# Main.net
KiCad netlist of a schematic drawn in EAGLE
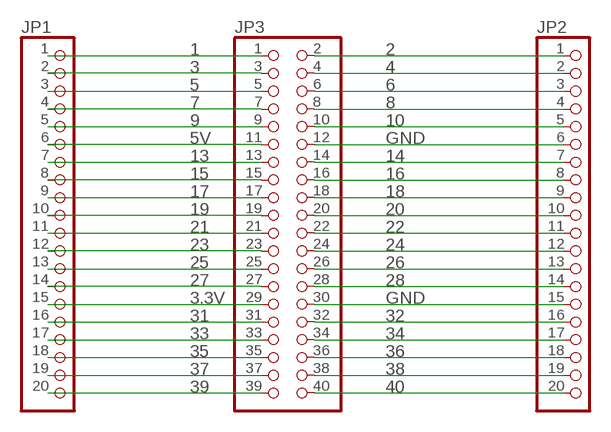
[diagram p0: schematic, sheet 1]

(export (version "E")
  (design (tool "Eeschema 10.0.6"))
  (components
    (comp (ref "JP1")
      (value "PINHD-1X20")
      (footprint "eagle-import:1X20")
      (libsource (lib "eagle-import") (part "PINHD-1X20"))
    )
    (comp (ref "JP2")
      (value "PINHD-1X20")
      (footprint "eagle-import:1X20")
      (libsource (lib "eagle-import") (part "PINHD-1X20"))
    )
    (comp (ref "JP3")
      (value "PINHD-2X20")
      (footprint "eagle-import:2X20")
      (libsource (lib "eagle-import") (part "PINHD-2X20"))
    )
  )
  (nets
    (net (code "1") (name "/1") (class "Default")
      (node (ref "JP1") (pin "1") (pinfunction "1_1") (pintype "passive"))
      (node (ref "JP3") (pin "1") (pinfunction "1_1") (pintype "passive"))
    )
    (net (code "2") (name "/2") (class "Default")
      (node (ref "JP2") (pin "1") (pinfunction "1_1") (pintype "passive"))
      (node (ref "JP3") (pin "2") (pinfunction "2_2") (pintype "passive"))
    )
    (net (code "3") (name "/3") (class "Default")
      (node (ref "JP1") (pin "2") (pinfunction "2_2") (pintype "passive"))
      (node (ref "JP3") (pin "3") (pinfunction "3_3") (pintype "passive"))
    )
    (net (code "4") (name "/3.3V") (class "Default")
      (node (ref "JP1") (pin "15") (pinfunction "15_15") (pintype "passive"))
      (node (ref "JP3") (pin "29") (pinfunction "29_29") (pintype "passive"))
    )
    (net (code "5") (name "/4") (class "Default")
      (node (ref "JP2") (pin "2") (pinfunction "2_2") (pintype "passive"))
      (node (ref "JP3") (pin "4") (pinfunction "4_4") (pintype "passive"))
    )
    (net (code "6") (name "/5") (class "Default")
      (node (ref "JP1") (pin "3") (pinfunction "3_3") (pintype "passive"))
      (node (ref "JP3") (pin "5") (pinfunction "5_5") (pintype "passive"))
    )
    (net (code "7") (name "/5V") (class "Default")
      (node (ref "JP1") (pin "6") (pinfunction "6_6") (pintype "passive"))
      (node (ref "JP3") (pin "11") (pinfunction "11_11") (pintype "passive"))
    )
    (net (code "8") (name "/6") (class "Default")
      (node (ref "JP2") (pin "3") (pinfunction "3_3") (pintype "passive"))
      (node (ref "JP3") (pin "6") (pinfunction "6_6") (pintype "passive"))
    )
    (net (code "9") (name "/7") (class "Default")
      (node (ref "JP1") (pin "4") (pinfunction "4_4") (pintype "passive"))
      (node (ref "JP3") (pin "7") (pinfunction "7_7") (pintype "passive"))
    )
    (net (code "10") (name "/8") (class "Default")
      (node (ref "JP2") (pin "4") (pinfunction "4_4") (pintype "passive"))
      (node (ref "JP3") (pin "8") (pinfunction "8_8") (pintype "passive"))
    )
    (net (code "11") (name "/9") (class "Default")
      (node (ref "JP1") (pin "5") (pinfunction "5_5") (pintype "passive"))
      (node (ref "JP3") (pin "9") (pinfunction "9_9") (pintype "passive"))
    )
    (net (code "12") (name "/10") (class "Default")
      (node (ref "JP2") (pin "5") (pinfunction "5_5") (pintype "passive"))
      (node (ref "JP3") (pin "10") (pinfunction "10_10") (pintype "passive"))
    )
    (net (code "13") (name "/13") (class "Default")
      (node (ref "JP1") (pin "7") (pinfunction "7_7") (pintype "passive"))
      (node (ref "JP3") (pin "13") (pinfunction "13_13") (pintype "passive"))
    )
    (net (code "14") (name "/14") (class "Default")
      (node (ref "JP2") (pin "7") (pinfunction "7_7") (pintype "passive"))
      (node (ref "JP3") (pin "14") (pinfunction "14_14") (pintype "passive"))
    )
    (net (code "15") (name "/15") (class "Default")
      (node (ref "JP1") (pin "8") (pinfunction "8_8") (pintype "passive"))
      (node (ref "JP3") (pin "15") (pinfunction "15_15") (pintype "passive"))
    )
    (net (code "16") (name "/16") (class "Default")
      (node (ref "JP2") (pin "8") (pinfunction "8_8") (pintype "passive"))
      (node (ref "JP3") (pin "16") (pinfunction "16_16") (pintype "passive"))
    )
    (net (code "17") (name "/17") (class "Default")
      (node (ref "JP1") (pin "9") (pinfunction "9_9") (pintype "passive"))
      (node (ref "JP3") (pin "17") (pinfunction "17_17") (pintype "passive"))
    )
    (net (code "18") (name "/18") (class "Default")
      (node (ref "JP2") (pin "9") (pinfunction "9_9") (pintype "passive"))
      (node (ref "JP3") (pin "18") (pinfunction "18_18") (pintype "passive"))
    )
    (net (code "19") (name "/19") (class "Default")
      (node (ref "JP1") (pin "10") (pinfunction "10_10") (pintype "passive"))
      (node (ref "JP3") (pin "19") (pinfunction "19_19") (pintype "passive"))
    )
    (net (code "20") (name "/20") (class "Default")
      (node (ref "JP2") (pin "10") (pinfunction "10_10") (pintype "passive"))
      (node (ref "JP3") (pin "20") (pinfunction "20_20") (pintype "passive"))
    )
    (net (code "21") (name "/21") (class "Default")
      (node (ref "JP1") (pin "11") (pinfunction "11_11") (pintype "passive"))
      (node (ref "JP3") (pin "21") (pinfunction "21_21") (pintype "passive"))
    )
    (net (code "22") (name "/22") (class "Default")
      (node (ref "JP2") (pin "11") (pinfunction "11_11") (pintype "passive"))
      (node (ref "JP3") (pin "22") (pinfunction "22_22") (pintype "passive"))
    )
    (net (code "23") (name "/23") (class "Default")
      (node (ref "JP1") (pin "12") (pinfunction "12_12") (pintype "passive"))
      (node (ref "JP3") (pin "23") (pinfunction "23_23") (pintype "passive"))
    )
    (net (code "24") (name "/24") (class "Default")
      (node (ref "JP2") (pin "12") (pinfunction "12_12") (pintype "passive"))
      (node (ref "JP3") (pin "24") (pinfunction "24_24") (pintype "passive"))
    )
    (net (code "25") (name "/25") (class "Default")
      (node (ref "JP1") (pin "13") (pinfunction "13_13") (pintype "passive"))
      (node (ref "JP3") (pin "25") (pinfunction "25_25") (pintype "passive"))
    )
    (net (code "26") (name "/26") (class "Default")
      (node (ref "JP2") (pin "13") (pinfunction "13_13") (pintype "passive"))
      (node (ref "JP3") (pin "26") (pinfunction "26_26") (pintype "passive"))
    )
    (net (code "27") (name "/27") (class "Default")
      (node (ref "JP1") (pin "14") (pinfunction "14_14") (pintype "passive"))
      (node (ref "JP3") (pin "27") (pinfunction "27_27") (pintype "passive"))
    )
    (net (code "28") (name "/28") (class "Default")
      (node (ref "JP2") (pin "14") (pinfunction "14_14") (pintype "passive"))
      (node (ref "JP3") (pin "28") (pinfunction "28_28") (pintype "passive"))
    )
    (net (code "29") (name "/31") (class "Default")
      (node (ref "JP1") (pin "16") (pinfunction "16_16") (pintype "passive"))
      (node (ref "JP3") (pin "31") (pinfunction "31_31") (pintype "passive"))
    )
    (net (code "30") (name "/32") (class "Default")
      (node (ref "JP2") (pin "16") (pinfunction "16_16") (pintype "passive"))
      (node (ref "JP3") (pin "32") (pinfunction "32_32") (pintype "passive"))
    )
    (net (code "31") (name "/33") (class "Default")
      (node (ref "JP1") (pin "17") (pinfunction "17_17") (pintype "passive"))
      (node (ref "JP3") (pin "33") (pinfunction "33_33") (pintype "passive"))
    )
    (net (code "32") (name "/34") (class "Default")
      (node (ref "JP2") (pin "17") (pinfunction "17_17") (pintype "passive"))
      (node (ref "JP3") (pin "34") (pinfunction "34_34") (pintype "passive"))
    )
    (net (code "33") (name "/35") (class "Default")
      (node (ref "JP1") (pin "18") (pinfunction "18_18") (pintype "passive"))
      (node (ref "JP3") (pin "35") (pinfunction "35_35") (pintype "passive"))
    )
    (net (code "34") (name "/36") (class "Default")
      (node (ref "JP2") (pin "18") (pinfunction "18_18") (pintype "passive"))
      (node (ref "JP3") (pin "36") (pinfunction "36_36") (pintype "passive"))
    )
    (net (code "35") (name "/37") (class "Default")
      (node (ref "JP1") (pin "19") (pinfunction "19_19") (pintype "passive"))
      (node (ref "JP3") (pin "37") (pinfunction "37_37") (pintype "passive"))
    )
    (net (code "36") (name "/38") (class "Default")
      (node (ref "JP2") (pin "19") (pinfunction "19_19") (pintype "passive"))
      (node (ref "JP3") (pin "38") (pinfunction "38_38") (pintype "passive"))
    )
    (net (code "37") (name "/39") (class "Default")
      (node (ref "JP1") (pin "20") (pinfunction "20_20") (pintype "passive"))
      (node (ref "JP3") (pin "39") (pinfunction "39_39") (pintype "passive"))
    )
    (net (code "38") (name "/40") (class "Default")
      (node (ref "JP2") (pin "20") (pinfunction "20_20") (pintype "passive"))
      (node (ref "JP3") (pin "40") (pinfunction "40_40") (pintype "passive"))
    )
    (net (code "39") (name "/GND") (class "Default")
      (node (ref "JP2") (pin "15") (pinfunction "15_15") (pintype "passive"))
      (node (ref "JP2") (pin "6") (pinfunction "6_6") (pintype "passive"))
      (node (ref "JP3") (pin "12") (pinfunction "12_12") (pintype "passive"))
      (node (ref "JP3") (pin "30") (pinfunction "30_30") (pintype "passive"))
    )
  )
)
